# MotorBoard.net
KiCad netlist of a schematic drawn in Altium Designer
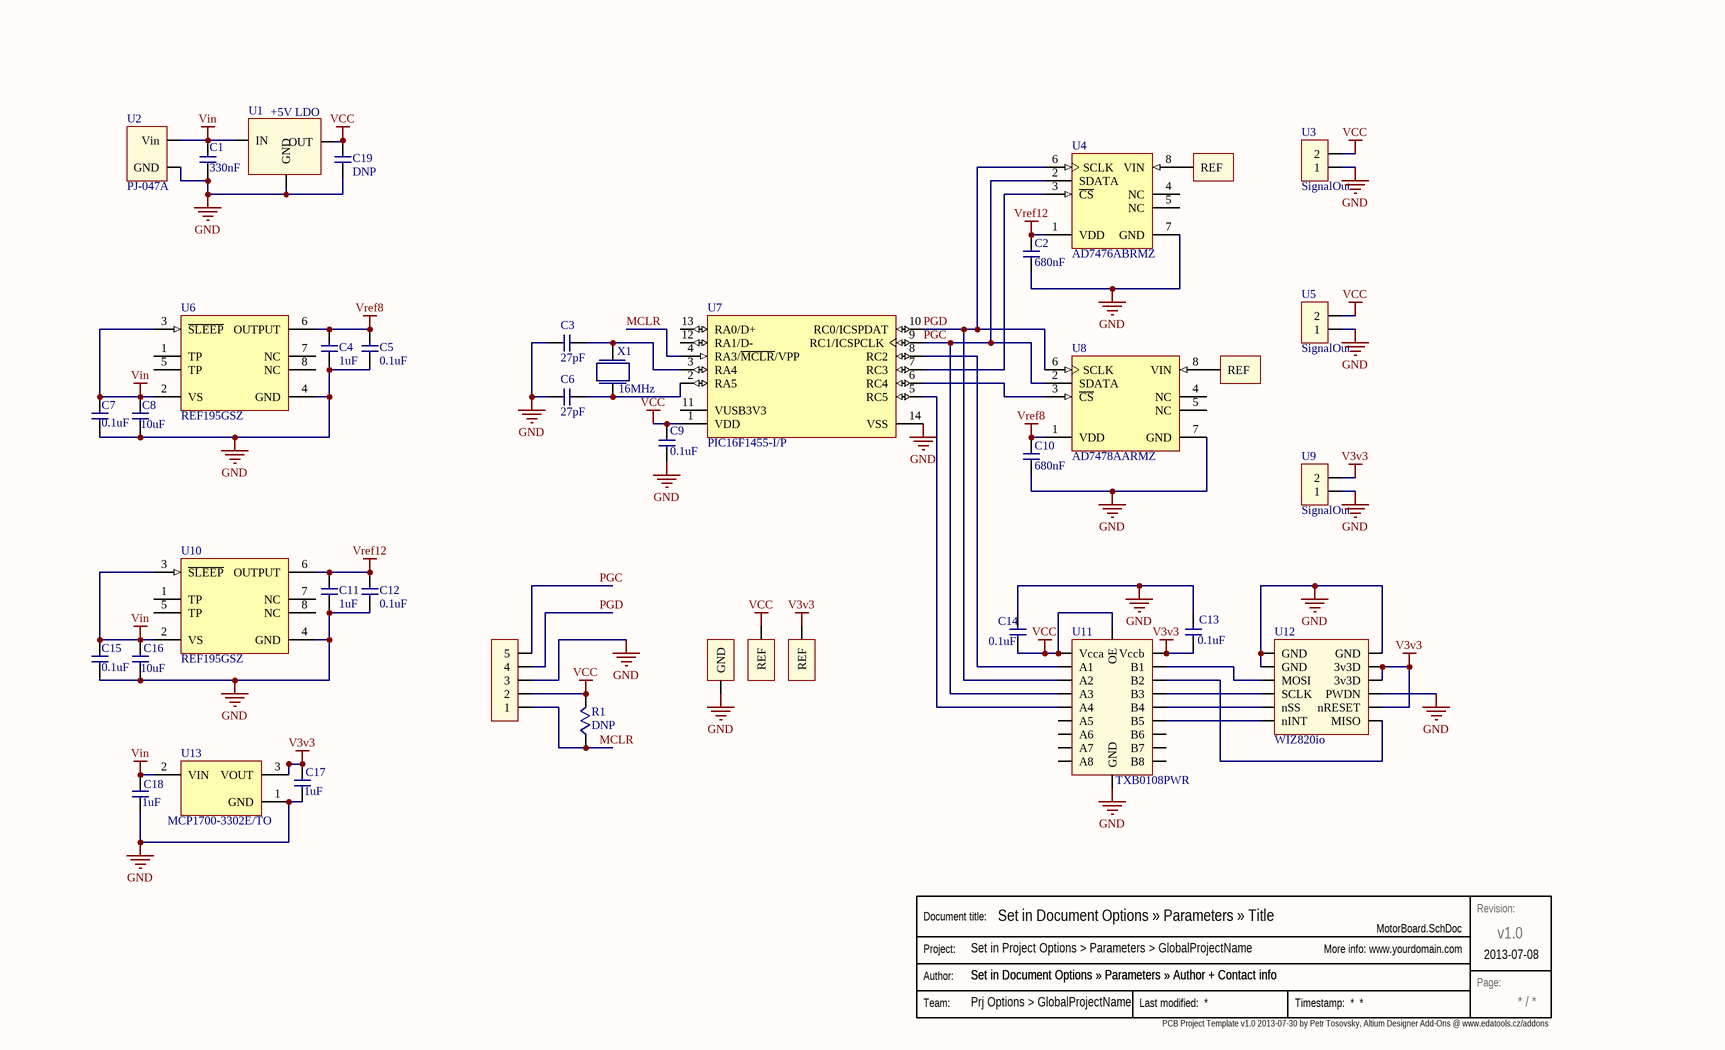
[diagram p0: MotorBoard.SchDoc]

(export (version "E")
  (design (tool "Eeschema 10.0.6"))
  (components
    (comp (ref "C1")
      (value "330nF")
      (footprint "FK18/24 Capacitor")
      (description "CAP CER 0.33UF 50V 10% RADIAL")
      (fields
        (field (name "MANUFACTURER") "TDK Corporation")
        (field (name "MANUFACTURER PART NUMBER") "FK24X7R1H334K")
      )
      (libsource (lib "Stamp") (part "FK24X7R1H334K"))
    )
    (comp (ref "C2")
      (value "680nF")
      (footprint "FK26/16 Capacitor")
      (description "CAP CER 0.68UF 50V 10% RADIAL")
      (fields
        (field (name "MANUFACTURER") "TDK Corporation")
        (field (name "MANUFACTURER PART NUMBER") "FK26X7R1H684K")
      )
      (libsource (lib "Stamp") (part "FK26X7R1H684K"))
    )
    (comp (ref "C3")
      (value "27pF")
      (footprint "FK18/24 Capacitor")
      (description "CAP CER 27PF 50V 5% RADIAL")
      (fields
        (field (name "MANUFACTURER") "TDK Corporation")
        (field (name "MANUFACTURER PART NUMBER") "FK18C0G1H270J")
      )
      (libsource (lib "Stamp") (part "FK18C0G1H270J"))
    )
    (comp (ref "C4")
      (value "1uF")
      (footprint "FK18/24 Capacitor")
      (description "CAP CER 1UF 50V 10% RADIAL")
      (fields
        (field (name "MANUFACTURER") "TDK Corporation")
        (field (name "MANUFACTURER PART NUMBER") "FK24X7R1H105K")
      )
      (libsource (lib "Stamp") (part "FK24X7R1H105K"))
    )
    (comp (ref "C5")
      (value "0.1uF")
      (footprint "FK26/16 Capacitor")
      (description "CAP CER 0.1UF 100V 10% RADIAL")
      (fields
        (field (name "MANUFACTURER") "TDK Corporation")
        (field (name "MANUFACTURER PART NUMBER") "FK26X7R2A104K")
      )
      (libsource (lib "Stamp") (part "FK26X7R2A104K"))
    )
    (comp (ref "C6")
      (value "27pF")
      (footprint "FK18/24 Capacitor")
      (description "CAP CER 27PF 50V 5% RADIAL")
      (fields
        (field (name "MANUFACTURER") "TDK Corporation")
        (field (name "MANUFACTURER PART NUMBER") "FK18C0G1H270J")
      )
      (libsource (lib "Stamp") (part "FK18C0G1H270J"))
    )
    (comp (ref "C7")
      (value "0.1uF")
      (footprint "FK26/16 Capacitor")
      (description "CAP CER 0.1UF 100V 10% RADIAL")
      (fields
        (field (name "MANUFACTURER") "TDK Corporation")
        (field (name "MANUFACTURER PART NUMBER") "FK26X7R2A104K")
      )
      (libsource (lib "Stamp") (part "FK26X7R2A104K"))
    )
    (comp (ref "C8")
      (value "10uF")
      (footprint "FK26/16 Capacitor")
      (description "CAP CER 10UF 16V 10% RADIAL")
      (fields
        (field (name "MANUFACTURER") "TDK Corporation")
        (field (name "MANUFACTURER PART NUMBER") "FK16X7R1C106K")
      )
      (libsource (lib "Stamp") (part "FK16X7R1C106K"))
    )
    (comp (ref "C9")
      (value "0.1uF")
      (footprint "FK26/16 Capacitor")
      (description "CAP CER 0.1UF 100V 10% RADIAL")
      (fields
        (field (name "MANUFACTURER") "TDK Corporation")
        (field (name "MANUFACTURER PART NUMBER") "FK26X7R2A104K")
      )
      (libsource (lib "Stamp") (part "FK26X7R2A104K"))
    )
    (comp (ref "C10")
      (value "680nF")
      (footprint "FK26/16 Capacitor")
      (description "CAP CER 0.68UF 50V 10% RADIAL")
      (fields
        (field (name "MANUFACTURER") "TDK Corporation")
        (field (name "MANUFACTURER PART NUMBER") "FK26X7R1H684K")
      )
      (libsource (lib "Stamp") (part "FK26X7R1H684K"))
    )
    (comp (ref "C11")
      (value "1uF")
      (footprint "FK18/24 Capacitor")
      (description "CAP CER 1UF 50V 10% RADIAL")
      (fields
        (field (name "MANUFACTURER") "TDK Corporation")
        (field (name "MANUFACTURER PART NUMBER") "FK24X7R1H105K")
      )
      (libsource (lib "Stamp") (part "FK24X7R1H105K"))
    )
    (comp (ref "C12")
      (value "0.1uF")
      (footprint "FK26/16 Capacitor")
      (description "CAP CER 0.1UF 100V 10% RADIAL")
      (fields
        (field (name "MANUFACTURER") "TDK Corporation")
        (field (name "MANUFACTURER PART NUMBER") "FK26X7R2A104K")
      )
      (libsource (lib "Stamp") (part "FK26X7R2A104K"))
    )
    (comp (ref "C13")
      (value "0.1uF")
      (footprint "FK26/16 Capacitor")
      (description "CAP CER 0.1UF 100V 10% RADIAL")
      (fields
        (field (name "MANUFACTURER") "TDK Corporation")
        (field (name "MANUFACTURER PART NUMBER") "FK26X7R2A104K")
      )
      (libsource (lib "Stamp") (part "FK26X7R2A104K"))
    )
    (comp (ref "C14")
      (value "0.1uF")
      (footprint "FK26/16 Capacitor")
      (description "CAP CER 0.1UF 100V 10% RADIAL")
      (fields
        (field (name "MANUFACTURER") "TDK Corporation")
        (field (name "MANUFACTURER PART NUMBER") "FK26X7R2A104K")
      )
      (libsource (lib "Stamp") (part "FK26X7R2A104K"))
    )
    (comp (ref "C15")
      (value "0.1uF")
      (footprint "FK26/16 Capacitor")
      (description "CAP CER 0.1UF 100V 10% RADIAL")
      (fields
        (field (name "MANUFACTURER") "TDK Corporation")
        (field (name "MANUFACTURER PART NUMBER") "FK26X7R2A104K")
      )
      (libsource (lib "Stamp") (part "FK26X7R2A104K"))
    )
    (comp (ref "C16")
      (value "10uF")
      (footprint "FK26/16 Capacitor")
      (description "CAP CER 10UF 16V 10% RADIAL")
      (fields
        (field (name "MANUFACTURER") "TDK Corporation")
        (field (name "MANUFACTURER PART NUMBER") "FK16X7R1C106K")
      )
      (libsource (lib "Stamp") (part "FK16X7R1C106K"))
    )
    (comp (ref "C17")
      (value "1uF")
      (footprint "FK18/24 Capacitor")
      (description "CAP CER 1UF 50V 10% RADIAL")
      (fields
        (field (name "MANUFACTURER") "TDK Corporation")
        (field (name "MANUFACTURER PART NUMBER") "FK24X7R1H105K")
      )
      (libsource (lib "Stamp") (part "FK24X7R1H105K"))
    )
    (comp (ref "C18")
      (value "1uF")
      (footprint "FK18/24 Capacitor")
      (description "CAP CER 1UF 50V 10% RADIAL")
      (fields
        (field (name "MANUFACTURER") "TDK Corporation")
        (field (name "MANUFACTURER PART NUMBER") "FK24X7R1H105K")
      )
      (libsource (lib "Stamp") (part "FK24X7R1H105K"))
    )
    (comp (ref "C19")
      (value "DNP")
      (footprint "FK26/16 Capacitor")
      (libsource (lib "Stamp") (part "DNP Cap"))
    )
    (comp (ref "R1") (value "DNP") (footprint "Axial 0.5") (libsource (lib "Stamp") (part "DNP Res")))
    (comp (ref "Stamp") (value "Stamp") (libsource (lib "ShieldsLib") (part "Stamp")))
    (comp (ref "U1")
      (value "+5V LDO")
      (footprint "MC7805CTG")
      (description "IC REG LDO 5V 1A TO220AB")
      (fields
        (field (name "MANUFACTURER") "ON Semiconductor")
        (field (name "MANUFACTURER PART NUMBER") "MC7805CTG")
      )
      (libsource (lib "Stamp") (part "MC7805CTG"))
    )
    (comp (ref "U2")
      (value "PJ-047A")
      (footprint "PJ-047A")
      (description "CON PWR JCK 2.0 X 6.0MM W/SHLD")
      (fields (field (name "MANUFACTURER") "CUI Inc"))
      (libsource (lib "Stamp") (part "PJ-047A"))
    )
    (comp (ref "U3") (value "SignalOut") (footprint "SignalOut") (libsource (lib "Stamp") (part "SignalOut")))
    (comp (ref "U4")
      (value "AD7476ABRMZ")
      (footprint "RM-8_L")
      (fields (field (name "GENERIC PART NUMBER") "AD7476A") (field (name "MANUFACTURER") "Analog Devices"))
      (libsource (lib "Analog Devices Data Converters Analog-to-Digital Converters") (part "AD7476ABRMZ"))
    )
    (comp (ref "U5") (value "SignalOut") (footprint "SignalOut") (libsource (lib "Stamp") (part "SignalOut")))
    (comp (ref "U6")
      (value "REF195GSZ")
      (footprint "ADI-R-8_L")
      (fields (field (name "MANUFACTURER") "Analog Devices"))
      (libsource (lib "Analog Devices Amplifiers and Linear Voltage References") (part "REF195GSZ"))
    )
    (comp (ref "U7")
      (value "PIC16F1455-I/P")
      (footprint "MCHP-PDIP-P14")
      (fields (field (name "MANUFACTURER") "Microchip"))
      (libsource (lib "Microchip PIC16") (part "PIC16F1455-I/P"))
    )
    (comp (ref "U8")
      (value "AD7478AARMZ")
      (footprint "RM-8_L")
      (fields (field (name "GENERIC PART NUMBER") "AD7478A") (field (name "MANUFACTURER") "Analog Devices"))
      (libsource (lib "Analog Devices Data Converters Analog-to-Digital Converters") (part "AD7478AARMZ"))
    )
    (comp (ref "U9") (value "SignalOut") (footprint "SignalOut") (libsource (lib "Stamp") (part "SignalOut")))
    (comp (ref "U10")
      (value "REF195GSZ")
      (footprint "ADI-R-8_L")
      (fields (field (name "MANUFACTURER") "Analog Devices"))
      (libsource (lib "Analog Devices Amplifiers and Linear Voltage References") (part "REF195GSZ"))
    )
    (comp (ref "U11")
      (value "TXB0108PWR")
      (footprint "TSOP65P640X120-20N")
      (description "IC 8-BIT TRNSTR 15KV ESD 20TSSOP")
      (fields (field (name "MANUFACTURER") "Texas Instruments"))
      (libsource (lib "Stamp") (part "TXB0108PWR"))
    )
    (comp (ref "U12")
      (value "WIZ820io")
      (footprint "WIZ5200")
      (description "Ethernet Modules W5200 & MAG JACK ioPLATFORM MODULE")
      (fields (field (name "MANUFACTURER") "WIZnet"))
      (libsource (lib "Stamp") (part "WIZ820io"))
    )
    (comp (ref "U13")
      (value "MCP1700-3302E/TO")
      (footprint "TO-92-TO3")
      (description "Low Quiescent Current LDO, 3-Pin TO-92, Extended TemperatureBAG")
      (fields (field (name "MANUFACTURER") "Microchip"))
      (libsource (lib "Microchip Power Management Line Regulator") (part "MCP1700-3302E/TO"))
    )
    (comp (ref "U14") (value "Ref") (footprint "Ground") (libsource (lib "") (part "Ref_1")))
    (comp (ref "U15") (value "Ref") (footprint "Ground") (libsource (lib "") (part "Ref_1")))
    (comp (ref "U16") (value "Ground") (footprint "Ground") (libsource (lib "Stamp") (part "Ground")))
    (comp (ref "U17")
      (value "ProgrammingHeader")
      (footprint "ProgrammingHeader")
      (libsource (lib "Stamp") (part "ProgrammingHeader"))
    )
    (comp (ref "U18") (value "Ref") (footprint "Ground") (libsource (lib "Stamp") (part "Ref")))
    (comp (ref "U19") (value "Ref") (footprint "Ground") (libsource (lib "Stamp") (part "Ref")))
    (comp (ref "X1")
      (value "16MHz")
      (footprint "9B-16.000MEEJ-B")
      (description "CRYSTAL 16MHZ 18PF THRU")
      (fields
        (field (name "MANUFACTURER") "TXC CORPORATION")
        (field (name "MANUFACTURER PART NUMBER") "9B-16.000MEEJ-B")
      )
      (libsource (lib "Stamp") (part "9B-16.000MEEJ-B"))
    )
  )
  (nets
    (net (code "1") (name "/MCLR") (class "Default")
      (node (ref "R1") (pin "1") (pinfunction "1_1") (pintype "passive"))
      (node (ref "U17") (pin "1") (pinfunction "1_1") (pintype "passive"))
      (node (ref "U7") (pin "4") (pinfunction "RA3/~{MCLR}/VPP_4") (pintype "input"))
    )
    (net (code "2") (name "/PGC") (class "Default")
      (node (ref "U11") (pin "4") (pinfunction "A3_4") (pintype "passive"))
      (node (ref "U17") (pin "5") (pinfunction "5_5") (pintype "passive"))
      (node (ref "U4") (pin "2") (pinfunction "SDATA_2") (pintype "tri_state"))
      (node (ref "U7") (pin "9") (pinfunction "RC1/ICSPCLK_9") (pintype "bidirectional"))
      (node (ref "U8") (pin "2") (pinfunction "SDATA_2") (pintype "tri_state"))
    )
    (net (code "3") (name "/PGD") (class "Default")
      (node (ref "U11") (pin "3") (pinfunction "A2_3") (pintype "passive"))
      (node (ref "U17") (pin "4") (pinfunction "4_4") (pintype "passive"))
      (node (ref "U4") (pin "6") (pinfunction "SCLK_6") (pintype "input"))
      (node (ref "U7") (pin "10") (pinfunction "RC0/ICSPDAT_10") (pintype "bidirectional"))
      (node (ref "U8") (pin "6") (pinfunction "SCLK_6") (pintype "input"))
    )
    (net (code "4") (name "GND") (class "Default")
      (node (ref "C1") (pin "1") (pinfunction "1_1") (pintype "passive"))
      (node (ref "C10") (pin "1") (pinfunction "1_1") (pintype "passive"))
      (node (ref "C11") (pin "1") (pinfunction "1_1") (pintype "passive"))
      (node (ref "C12") (pin "1") (pinfunction "1_1") (pintype "passive"))
      (node (ref "C13") (pin "1") (pinfunction "1_1") (pintype "passive"))
      (node (ref "C14") (pin "2") (pinfunction "2_2") (pintype "passive"))
      (node (ref "C15") (pin "1") (pinfunction "1_1") (pintype "passive"))
      (node (ref "C16") (pin "1") (pinfunction "1_1") (pintype "passive"))
      (node (ref "C17") (pin "1") (pinfunction "1_1") (pintype "passive"))
      (node (ref "C18") (pin "1") (pinfunction "1_1") (pintype "passive"))
      (node (ref "C19") (pin "1") (pinfunction "1_1") (pintype "passive"))
      (node (ref "C2") (pin "1") (pinfunction "1_1") (pintype "passive"))
      (node (ref "C3") (pin "1") (pinfunction "1_1") (pintype "passive"))
      (node (ref "C4") (pin "1") (pinfunction "1_1") (pintype "passive"))
      (node (ref "C5") (pin "1") (pinfunction "1_1") (pintype "passive"))
      (node (ref "C6") (pin "1") (pinfunction "1_1") (pintype "passive"))
      (node (ref "C7") (pin "1") (pinfunction "1_1") (pintype "passive"))
      (node (ref "C8") (pin "1") (pinfunction "1_1") (pintype "passive"))
      (node (ref "C9") (pin "1") (pinfunction "1_1") (pintype "passive"))
      (node (ref "U1") (pin "2") (pinfunction "GND_2") (pintype "passive"))
      (node (ref "U10") (pin "4") (pinfunction "GND_4") (pintype "power_in"))
      (node (ref "U11") (pin "11") (pinfunction "GND_11") (pintype "passive"))
      (node (ref "U12") (pin "1") (pinfunction "GND_1") (pintype "passive"))
      (node (ref "U12") (pin "12") (pinfunction "GND_12") (pintype "passive"))
      (node (ref "U12") (pin "2") (pinfunction "GND_2") (pintype "passive"))
      (node (ref "U12") (pin "9") (pinfunction "PWDN_9") (pintype "passive"))
      (node (ref "U13") (pin "1") (pinfunction "GND_1") (pintype "power_in"))
      (node (ref "U16") (pin "1") (pinfunction "GND_1") (pintype "passive"))
      (node (ref "U17") (pin "3") (pinfunction "3_3") (pintype "passive"))
      (node (ref "U2") (pin "2") (pinfunction "GND_2") (pintype "passive"))
      (node (ref "U3") (pin "1") (pinfunction "1_1") (pintype "passive"))
      (node (ref "U4") (pin "7") (pinfunction "GND_7") (pintype "power_in"))
      (node (ref "U5") (pin "1") (pinfunction "1_1") (pintype "passive"))
      (node (ref "U6") (pin "4") (pinfunction "GND_4") (pintype "power_in"))
      (node (ref "U7") (pin "14") (pinfunction "VSS_14") (pintype "power_in"))
      (node (ref "U8") (pin "7") (pinfunction "GND_7") (pintype "power_in"))
      (node (ref "U9") (pin "1") (pinfunction "1_1") (pintype "passive"))
    )
    (net (code "5") (name "Net-(U4-~{CS})") (class "Default")
      (node (ref "U4") (pin "3") (pinfunction "~{CS}_3") (pintype "input"))
      (node (ref "U7") (pin "7") (pinfunction "RC3_7") (pintype "bidirectional"))
    )
    (net (code "6") (name "Net-(U7-RA4)") (class "Default")
      (node (ref "C3") (pin "2") (pinfunction "2_2") (pintype "passive"))
      (node (ref "U7") (pin "3") (pinfunction "RA4_3") (pintype "bidirectional"))
      (node (ref "X1") (pin "2") (pinfunction "2_2") (pintype "passive"))
    )
    (net (code "7") (name "Net-(U7-RA5)") (class "Default")
      (node (ref "C6") (pin "2") (pinfunction "2_2") (pintype "passive"))
      (node (ref "U7") (pin "2") (pinfunction "RA5_2") (pintype "bidirectional"))
      (node (ref "X1") (pin "1") (pinfunction "1_1") (pintype "passive"))
    )
    (net (code "8") (name "Net-(U7-RC4)") (class "Default")
      (node (ref "U7") (pin "6") (pinfunction "RC4_6") (pintype "bidirectional"))
      (node (ref "U8") (pin "3") (pinfunction "~{CS}_3") (pintype "input"))
    )
    (net (code "9") (name "Net-(U11-A1)") (class "Default")
      (node (ref "U11") (pin "1") (pinfunction "A1_1") (pintype "passive"))
      (node (ref "U7") (pin "8") (pinfunction "RC2_8") (pintype "bidirectional"))
    )
    (net (code "10") (name "Net-(U11-A4)") (class "Default")
      (node (ref "U11") (pin "5") (pinfunction "A4_5") (pintype "passive"))
      (node (ref "U7") (pin "5") (pinfunction "RC5_5") (pintype "bidirectional"))
    )
    (net (code "11") (name "Net-(U11-B1)") (class "Default")
      (node (ref "U11") (pin "20") (pinfunction "B1_20") (pintype "passive"))
      (node (ref "U12") (pin "3") (pinfunction "MOSI_3") (pintype "passive"))
    )
    (net (code "12") (name "Net-(U11-B2)") (class "Default")
      (node (ref "U11") (pin "18") (pinfunction "B2_18") (pintype "passive"))
      (node (ref "U12") (pin "7") (pinfunction "MISO_7") (pintype "passive"))
    )
    (net (code "13") (name "Net-(U11-B3)") (class "Default")
      (node (ref "U11") (pin "17") (pinfunction "B3_17") (pintype "passive"))
      (node (ref "U12") (pin "4") (pinfunction "SCLK_4") (pintype "passive"))
    )
    (net (code "14") (name "Net-(U11-B4)") (class "Default")
      (node (ref "U11") (pin "16") (pinfunction "B4_16") (pintype "passive"))
      (node (ref "U12") (pin "5") (pinfunction "nSS_5") (pintype "passive"))
    )
    (net (code "15") (name "Net-(U11-B5)") (class "Default")
      (node (ref "U11") (pin "15") (pinfunction "B5_15") (pintype "passive"))
      (node (ref "U12") (pin "6") (pinfunction "nINT_6") (pintype "passive"))
    )
    (net (code "16") (name "Net-(U18-REF)") (class "Default")
      (node (ref "U18") (pin "1") (pinfunction "REF_1") (pintype "passive"))
      (node (ref "U4") (pin "8") (pinfunction "VIN_8") (pintype "input"))
    )
    (net (code "17") (name "Net-(U19-REF)") (class "Default")
      (node (ref "U19") (pin "1") (pinfunction "REF_1") (pintype "passive"))
      (node (ref "U8") (pin "8") (pinfunction "VIN_8") (pintype "input"))
    )
    (net (code "18") (name "V3v3") (class "Default")
      (node (ref "C13") (pin "2") (pinfunction "2_2") (pintype "passive"))
      (node (ref "C17") (pin "2") (pinfunction "2_2") (pintype "passive"))
      (node (ref "U11") (pin "19") (pinfunction "Vccb_19") (pintype "passive"))
      (node (ref "U12") (pin "10") (pinfunction "3v3D_10") (pintype "passive"))
      (node (ref "U12") (pin "11") (pinfunction "3v3D_11") (pintype "passive"))
      (node (ref "U12") (pin "8") (pinfunction "nRESET_8") (pintype "passive"))
      (node (ref "U13") (pin "3") (pinfunction "VOUT_3") (pintype "power_in"))
      (node (ref "U15") (pin "1") (pinfunction "REF_1") (pintype "passive"))
      (node (ref "U9") (pin "2") (pinfunction "2_2") (pintype "passive"))
    )
    (net (code "19") (name "VCC") (class "Default")
      (node (ref "C14") (pin "1") (pinfunction "1_1") (pintype "passive"))
      (node (ref "C19") (pin "2") (pinfunction "2_2") (pintype "passive"))
      (node (ref "C9") (pin "2") (pinfunction "2_2") (pintype "passive"))
      (node (ref "R1") (pin "2") (pinfunction "2_2") (pintype "passive"))
      (node (ref "U1") (pin "3") (pinfunction "OUT_3") (pintype "passive"))
      (node (ref "U11") (pin "10") (pinfunction "OE_10") (pintype "passive"))
      (node (ref "U11") (pin "2") (pinfunction "Vcca_2") (pintype "passive"))
      (node (ref "U14") (pin "1") (pinfunction "REF_1") (pintype "passive"))
      (node (ref "U17") (pin "2") (pinfunction "2_2") (pintype "passive"))
      (node (ref "U3") (pin "2") (pinfunction "2_2") (pintype "passive"))
      (node (ref "U5") (pin "2") (pinfunction "2_2") (pintype "passive"))
      (node (ref "U7") (pin "1") (pinfunction "VDD_1") (pintype "power_in"))
    )
    (net (code "20") (name "Vin") (class "Default")
      (node (ref "C1") (pin "2") (pinfunction "2_2") (pintype "passive"))
      (node (ref "C15") (pin "2") (pinfunction "2_2") (pintype "passive"))
      (node (ref "C16") (pin "2") (pinfunction "2_2") (pintype "passive"))
      (node (ref "C18") (pin "2") (pinfunction "2_2") (pintype "passive"))
      (node (ref "C7") (pin "2") (pinfunction "2_2") (pintype "passive"))
      (node (ref "C8") (pin "2") (pinfunction "2_2") (pintype "passive"))
      (node (ref "U1") (pin "1") (pinfunction "IN_1") (pintype "passive"))
      (node (ref "U10") (pin "2") (pinfunction "VS_2") (pintype "power_in"))
      (node (ref "U10") (pin "3") (pinfunction "~{SLEEP}_3") (pintype "input"))
      (node (ref "U13") (pin "2") (pinfunction "VIN_2") (pintype "power_in"))
      (node (ref "U2") (pin "1") (pinfunction "Vin_1") (pintype "passive"))
      (node (ref "U6") (pin "2") (pinfunction "VS_2") (pintype "power_in"))
      (node (ref "U6") (pin "3") (pinfunction "~{SLEEP}_3") (pintype "input"))
    )
    (net (code "21") (name "Vref8") (class "Default")
      (node (ref "C10") (pin "2") (pinfunction "2_2") (pintype "passive"))
      (node (ref "C4") (pin "2") (pinfunction "2_2") (pintype "passive"))
      (node (ref "C5") (pin "2") (pinfunction "2_2") (pintype "passive"))
      (node (ref "U6") (pin "6") (pinfunction "OUTPUT_6") (pintype "tri_state"))
      (node (ref "U8") (pin "1") (pinfunction "VDD_1") (pintype "power_in"))
    )
    (net (code "22") (name "Vref12") (class "Default")
      (node (ref "C11") (pin "2") (pinfunction "2_2") (pintype "passive"))
      (node (ref "C12") (pin "2") (pinfunction "2_2") (pintype "passive"))
      (node (ref "C2") (pin "2") (pinfunction "2_2") (pintype "passive"))
      (node (ref "U10") (pin "6") (pinfunction "OUTPUT_6") (pintype "tri_state"))
      (node (ref "U4") (pin "1") (pinfunction "VDD_1") (pintype "power_in"))
    )
    (net (code "23") (name "unconnected-(U4-NC-Pad4)") (class "Default")
      (node (ref "U4") (pin "4") (pinfunction "NC_4") (pintype "passive"))
    )
    (net (code "24") (name "unconnected-(U4-NC-Pad5)") (class "Default")
      (node (ref "U4") (pin "5") (pinfunction "NC_5") (pintype "passive"))
    )
    (net (code "25") (name "unconnected-(U6-NC-Pad7)") (class "Default")
      (node (ref "U6") (pin "7") (pinfunction "NC_7") (pintype "passive"))
    )
    (net (code "26") (name "unconnected-(U6-NC-Pad8)") (class "Default")
      (node (ref "U6") (pin "8") (pinfunction "NC_8") (pintype "passive"))
    )
    (net (code "27") (name "unconnected-(U6-TP-Pad1)") (class "Default")
      (node (ref "U6") (pin "1") (pinfunction "TP_1") (pintype "passive"))
    )
    (net (code "28") (name "unconnected-(U6-TP-Pad5)") (class "Default")
      (node (ref "U6") (pin "5") (pinfunction "TP_5") (pintype "passive"))
    )
    (net (code "29") (name "unconnected-(U7-RA0{slash}D+-Pad13)") (class "Default")
      (node (ref "U7") (pin "13") (pinfunction "RA0/D+_13") (pintype "bidirectional"))
    )
    (net (code "30") (name "unconnected-(U7-RA1{slash}D--Pad12)") (class "Default")
      (node (ref "U7") (pin "12") (pinfunction "RA1/D-_12") (pintype "bidirectional"))
    )
    (net (code "31") (name "unconnected-(U7-VUSB3V3-Pad11)") (class "Default")
      (node (ref "U7") (pin "11") (pinfunction "VUSB3V3_11") (pintype "power_in"))
    )
    (net (code "32") (name "unconnected-(U8-NC-Pad4)") (class "Default")
      (node (ref "U8") (pin "4") (pinfunction "NC_4") (pintype "passive"))
    )
    (net (code "33") (name "unconnected-(U8-NC-Pad5)") (class "Default")
      (node (ref "U8") (pin "5") (pinfunction "NC_5") (pintype "passive"))
    )
    (net (code "34") (name "unconnected-(U10-NC-Pad7)") (class "Default")
      (node (ref "U10") (pin "7") (pinfunction "NC_7") (pintype "passive"))
    )
    (net (code "35") (name "unconnected-(U10-NC-Pad8)") (class "Default")
      (node (ref "U10") (pin "8") (pinfunction "NC_8") (pintype "passive"))
    )
    (net (code "36") (name "unconnected-(U10-TP-Pad1)") (class "Default")
      (node (ref "U10") (pin "1") (pinfunction "TP_1") (pintype "passive"))
    )
    (net (code "37") (name "unconnected-(U10-TP-Pad5)") (class "Default")
      (node (ref "U10") (pin "5") (pinfunction "TP_5") (pintype "passive"))
    )
    (net (code "38") (name "unconnected-(U11-A5-Pad6)") (class "Default")
      (node (ref "U11") (pin "6") (pinfunction "A5_6") (pintype "passive"))
    )
    (net (code "39") (name "unconnected-(U11-A6-Pad7)") (class "Default")
      (node (ref "U11") (pin "7") (pinfunction "A6_7") (pintype "passive"))
    )
    (net (code "40") (name "unconnected-(U11-A7-Pad8)") (class "Default")
      (node (ref "U11") (pin "8") (pinfunction "A7_8") (pintype "passive"))
    )
    (net (code "41") (name "unconnected-(U11-A8-Pad9)") (class "Default")
      (node (ref "U11") (pin "9") (pinfunction "A8_9") (pintype "passive"))
    )
    (net (code "42") (name "unconnected-(U11-B6-Pad14)") (class "Default")
      (node (ref "U11") (pin "14") (pinfunction "B6_14") (pintype "passive"))
    )
    (net (code "43") (name "unconnected-(U11-B7-Pad13)") (class "Default")
      (node (ref "U11") (pin "13") (pinfunction "B7_13") (pintype "passive"))
    )
    (net (code "44") (name "unconnected-(U11-B8-Pad12)") (class "Default")
      (node (ref "U11") (pin "12") (pinfunction "B8_12") (pintype "passive"))
    )
  )
)
